# motores.net
KiCad netlist of a schematic drawn in EAGLE
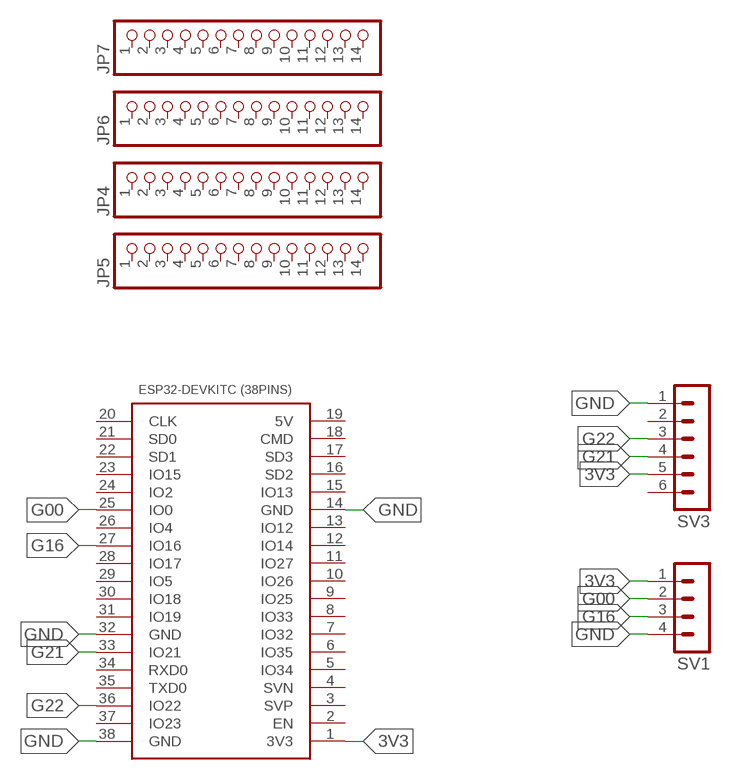
[diagram p0: schematic, sheet 1]

(export (version "E")
  (design (tool "Eeschema 10.0.6"))
  (components
    (comp (ref "ESP32-DEVKITC(38PINS)1")
      (value "ESP32DEVKITC_38PINS")
      (footprint "eagle-import:ESP32-DEVKITC")
      (libsource (lib "eagle-import") (part "ESP32DEVKITC_38PINS"))
    )
    (comp (ref "JP4")
      (value "PINHD-1X14")
      (footprint "eagle-import:1X14")
      (libsource (lib "eagle-import") (part "PINHD-1X14"))
    )
    (comp (ref "JP5")
      (value "PINHD-1X14")
      (footprint "eagle-import:1X14")
      (libsource (lib "eagle-import") (part "PINHD-1X14"))
    )
    (comp (ref "JP6")
      (value "PINHD-1X14")
      (footprint "eagle-import:1X14")
      (libsource (lib "eagle-import") (part "PINHD-1X14"))
    )
    (comp (ref "JP7")
      (value "PINHD-1X14")
      (footprint "eagle-import:1X14")
      (libsource (lib "eagle-import") (part "PINHD-1X14"))
    )
    (comp (ref "SV1")
      (value "MA04-1")
      (footprint "eagle-import:MA04-1")
      (libsource (lib "eagle-import") (part "MA04-1"))
    )
    (comp (ref "SV3")
      (value "MA06-1")
      (footprint "eagle-import:MA06-1")
      (libsource (lib "eagle-import") (part "MA06-1"))
    )
  )
  (nets
    (net (code "1") (name "3V3") (class "Default")
      (node (ref "ESP32-DEVKITC(38PINS)1") (pin "1") (pinfunction "3V3_1") (pintype "bidirectional"))
      (node (ref "SV1") (pin "1") (pinfunction "1_1") (pintype "passive"))
      (node (ref "SV3") (pin "5") (pinfunction "5_5") (pintype "passive"))
    )
    (net (code "2") (name "G00") (class "Default")
      (node (ref "ESP32-DEVKITC(38PINS)1") (pin "25") (pinfunction "IO0_25") (pintype "bidirectional"))
      (node (ref "SV1") (pin "2") (pinfunction "2_2") (pintype "passive"))
    )
    (net (code "3") (name "G16") (class "Default")
      (node (ref "ESP32-DEVKITC(38PINS)1") (pin "27") (pinfunction "IO16_27") (pintype "bidirectional"))
      (node (ref "SV1") (pin "3") (pinfunction "3_3") (pintype "passive"))
    )
    (net (code "4") (name "G21") (class "Default")
      (node (ref "ESP32-DEVKITC(38PINS)1") (pin "33") (pinfunction "IO21_33") (pintype "bidirectional"))
      (node (ref "SV3") (pin "4") (pinfunction "4_4") (pintype "passive"))
    )
    (net (code "5") (name "G22") (class "Default")
      (node (ref "ESP32-DEVKITC(38PINS)1") (pin "36") (pinfunction "IO22_36") (pintype "bidirectional"))
      (node (ref "SV3") (pin "3") (pinfunction "3_3") (pintype "passive"))
    )
    (net (code "6") (name "GND") (class "Default")
      (node (ref "ESP32-DEVKITC(38PINS)1") (pin "14") (pinfunction "GND_14") (pintype "bidirectional"))
      (node (ref "ESP32-DEVKITC(38PINS)1") (pin "32") (pinfunction "GND_32") (pintype "bidirectional"))
      (node (ref "ESP32-DEVKITC(38PINS)1") (pin "38") (pinfunction "GND_38") (pintype "bidirectional"))
      (node (ref "SV1") (pin "4") (pinfunction "4_4") (pintype "passive"))
      (node (ref "SV3") (pin "1") (pinfunction "1_1") (pintype "passive"))
    )
    (net (code "7") (name "unconnected-(ESP32-DEVKITC(38PINS)1-5V-Pad19)") (class "Default")
      (node (ref "ESP32-DEVKITC(38PINS)1") (pin "19") (pinfunction "5V_19") (pintype "bidirectional"))
    )
    (net (code "8") (name "unconnected-(ESP32-DEVKITC(38PINS)1-CLK-Pad20)") (class "Default")
      (node (ref "ESP32-DEVKITC(38PINS)1") (pin "20") (pinfunction "CLK_20") (pintype "bidirectional"))
    )
    (net (code "9") (name "unconnected-(ESP32-DEVKITC(38PINS)1-CMD-Pad18)") (class "Default")
      (node (ref "ESP32-DEVKITC(38PINS)1") (pin "18") (pinfunction "CMD_18") (pintype "bidirectional"))
    )
    (net (code "10") (name "unconnected-(ESP32-DEVKITC(38PINS)1-EN-Pad2)") (class "Default")
      (node (ref "ESP32-DEVKITC(38PINS)1") (pin "2") (pinfunction "EN_2") (pintype "bidirectional"))
    )
    (net (code "11") (name "unconnected-(ESP32-DEVKITC(38PINS)1-IO2-Pad24)") (class "Default")
      (node (ref "ESP32-DEVKITC(38PINS)1") (pin "24") (pinfunction "IO2_24") (pintype "bidirectional"))
    )
    (net (code "12") (name "unconnected-(ESP32-DEVKITC(38PINS)1-IO4-Pad26)") (class "Default")
      (node (ref "ESP32-DEVKITC(38PINS)1") (pin "26") (pinfunction "IO4_26") (pintype "bidirectional"))
    )
    (net (code "13") (name "unconnected-(ESP32-DEVKITC(38PINS)1-IO5-Pad29)") (class "Default")
      (node (ref "ESP32-DEVKITC(38PINS)1") (pin "29") (pinfunction "IO5_29") (pintype "bidirectional"))
    )
    (net (code "14") (name "unconnected-(ESP32-DEVKITC(38PINS)1-IO12-Pad13)") (class "Default")
      (node (ref "ESP32-DEVKITC(38PINS)1") (pin "13") (pinfunction "IO12_13") (pintype "bidirectional"))
    )
    (net (code "15") (name "unconnected-(ESP32-DEVKITC(38PINS)1-IO13-Pad15)") (class "Default")
      (node (ref "ESP32-DEVKITC(38PINS)1") (pin "15") (pinfunction "IO13_15") (pintype "bidirectional"))
    )
    (net (code "16") (name "unconnected-(ESP32-DEVKITC(38PINS)1-IO14-Pad12)") (class "Default")
      (node (ref "ESP32-DEVKITC(38PINS)1") (pin "12") (pinfunction "IO14_12") (pintype "bidirectional"))
    )
    (net (code "17") (name "unconnected-(ESP32-DEVKITC(38PINS)1-IO15-Pad23)") (class "Default")
      (node (ref "ESP32-DEVKITC(38PINS)1") (pin "23") (pinfunction "IO15_23") (pintype "bidirectional"))
    )
    (net (code "18") (name "unconnected-(ESP32-DEVKITC(38PINS)1-IO17-Pad28)") (class "Default")
      (node (ref "ESP32-DEVKITC(38PINS)1") (pin "28") (pinfunction "IO17_28") (pintype "bidirectional"))
    )
    (net (code "19") (name "unconnected-(ESP32-DEVKITC(38PINS)1-IO18-Pad30)") (class "Default")
      (node (ref "ESP32-DEVKITC(38PINS)1") (pin "30") (pinfunction "IO18_30") (pintype "bidirectional"))
    )
    (net (code "20") (name "unconnected-(ESP32-DEVKITC(38PINS)1-IO19-Pad31)") (class "Default")
      (node (ref "ESP32-DEVKITC(38PINS)1") (pin "31") (pinfunction "IO19_31") (pintype "bidirectional"))
    )
    (net (code "21") (name "unconnected-(ESP32-DEVKITC(38PINS)1-IO23-Pad37)") (class "Default")
      (node (ref "ESP32-DEVKITC(38PINS)1") (pin "37") (pinfunction "IO23_37") (pintype "bidirectional"))
    )
    (net (code "22") (name "unconnected-(ESP32-DEVKITC(38PINS)1-IO25-Pad9)") (class "Default")
      (node (ref "ESP32-DEVKITC(38PINS)1") (pin "9") (pinfunction "IO25_9") (pintype "bidirectional"))
    )
    (net (code "23") (name "unconnected-(ESP32-DEVKITC(38PINS)1-IO26-Pad10)") (class "Default")
      (node (ref "ESP32-DEVKITC(38PINS)1") (pin "10") (pinfunction "IO26_10") (pintype "bidirectional"))
    )
    (net (code "24") (name "unconnected-(ESP32-DEVKITC(38PINS)1-IO27-Pad11)") (class "Default")
      (node (ref "ESP32-DEVKITC(38PINS)1") (pin "11") (pinfunction "IO27_11") (pintype "bidirectional"))
    )
    (net (code "25") (name "unconnected-(ESP32-DEVKITC(38PINS)1-IO32-Pad7)") (class "Default")
      (node (ref "ESP32-DEVKITC(38PINS)1") (pin "7") (pinfunction "IO32_7") (pintype "bidirectional"))
    )
    (net (code "26") (name "unconnected-(ESP32-DEVKITC(38PINS)1-IO33-Pad8)") (class "Default")
      (node (ref "ESP32-DEVKITC(38PINS)1") (pin "8") (pinfunction "IO33_8") (pintype "bidirectional"))
    )
    (net (code "27") (name "unconnected-(ESP32-DEVKITC(38PINS)1-IO34-Pad5)") (class "Default")
      (node (ref "ESP32-DEVKITC(38PINS)1") (pin "5") (pinfunction "IO34_5") (pintype "bidirectional"))
    )
    (net (code "28") (name "unconnected-(ESP32-DEVKITC(38PINS)1-IO35-Pad6)") (class "Default")
      (node (ref "ESP32-DEVKITC(38PINS)1") (pin "6") (pinfunction "IO35_6") (pintype "bidirectional"))
    )
    (net (code "29") (name "unconnected-(ESP32-DEVKITC(38PINS)1-RXD0-Pad34)") (class "Default")
      (node (ref "ESP32-DEVKITC(38PINS)1") (pin "34") (pinfunction "RXD0_34") (pintype "bidirectional"))
    )
    (net (code "30") (name "unconnected-(ESP32-DEVKITC(38PINS)1-SD0-Pad21)") (class "Default")
      (node (ref "ESP32-DEVKITC(38PINS)1") (pin "21") (pinfunction "SD0_21") (pintype "bidirectional"))
    )
    (net (code "31") (name "unconnected-(ESP32-DEVKITC(38PINS)1-SD1-Pad22)") (class "Default")
      (node (ref "ESP32-DEVKITC(38PINS)1") (pin "22") (pinfunction "SD1_22") (pintype "bidirectional"))
    )
    (net (code "32") (name "unconnected-(ESP32-DEVKITC(38PINS)1-SD2-Pad16)") (class "Default")
      (node (ref "ESP32-DEVKITC(38PINS)1") (pin "16") (pinfunction "SD2_16") (pintype "bidirectional"))
    )
    (net (code "33") (name "unconnected-(ESP32-DEVKITC(38PINS)1-SD3-Pad17)") (class "Default")
      (node (ref "ESP32-DEVKITC(38PINS)1") (pin "17") (pinfunction "SD3_17") (pintype "bidirectional"))
    )
    (net (code "34") (name "unconnected-(ESP32-DEVKITC(38PINS)1-SVN-Pad4)") (class "Default")
      (node (ref "ESP32-DEVKITC(38PINS)1") (pin "4") (pinfunction "SVN_4") (pintype "bidirectional"))
    )
    (net (code "35") (name "unconnected-(ESP32-DEVKITC(38PINS)1-SVP-Pad3)") (class "Default")
      (node (ref "ESP32-DEVKITC(38PINS)1") (pin "3") (pinfunction "SVP_3") (pintype "bidirectional"))
    )
    (net (code "36") (name "unconnected-(ESP32-DEVKITC(38PINS)1-TXD0-Pad35)") (class "Default")
      (node (ref "ESP32-DEVKITC(38PINS)1") (pin "35") (pinfunction "TXD0_35") (pintype "bidirectional"))
    )
    (net (code "37") (name "unconnected-(JP4-Pad1)") (class "Default")
      (node (ref "JP4") (pin "1") (pinfunction "1_1") (pintype "passive"))
    )
    (net (code "38") (name "unconnected-(JP4-Pad2)") (class "Default")
      (node (ref "JP4") (pin "2") (pinfunction "2_2") (pintype "passive"))
    )
    (net (code "39") (name "unconnected-(JP4-Pad3)") (class "Default")
      (node (ref "JP4") (pin "3") (pinfunction "3_3") (pintype "passive"))
    )
    (net (code "40") (name "unconnected-(JP4-Pad4)") (class "Default")
      (node (ref "JP4") (pin "4") (pinfunction "4_4") (pintype "passive"))
    )
    (net (code "41") (name "unconnected-(JP4-Pad5)") (class "Default")
      (node (ref "JP4") (pin "5") (pinfunction "5_5") (pintype "passive"))
    )
    (net (code "42") (name "unconnected-(JP4-Pad6)") (class "Default")
      (node (ref "JP4") (pin "6") (pinfunction "6_6") (pintype "passive"))
    )
    (net (code "43") (name "unconnected-(JP4-Pad7)") (class "Default")
      (node (ref "JP4") (pin "7") (pinfunction "7_7") (pintype "passive"))
    )
    (net (code "44") (name "unconnected-(JP4-Pad8)") (class "Default")
      (node (ref "JP4") (pin "8") (pinfunction "8_8") (pintype "passive"))
    )
    (net (code "45") (name "unconnected-(JP4-Pad9)") (class "Default")
      (node (ref "JP4") (pin "9") (pinfunction "9_9") (pintype "passive"))
    )
    (net (code "46") (name "unconnected-(JP4-Pad10)") (class "Default")
      (node (ref "JP4") (pin "10") (pinfunction "10_10") (pintype "passive"))
    )
    (net (code "47") (name "unconnected-(JP4-Pad11)") (class "Default")
      (node (ref "JP4") (pin "11") (pinfunction "11_11") (pintype "passive"))
    )
    (net (code "48") (name "unconnected-(JP4-Pad12)") (class "Default")
      (node (ref "JP4") (pin "12") (pinfunction "12_12") (pintype "passive"))
    )
    (net (code "49") (name "unconnected-(JP4-Pad13)") (class "Default")
      (node (ref "JP4") (pin "13") (pinfunction "13_13") (pintype "passive"))
    )
    (net (code "50") (name "unconnected-(JP4-Pad14)") (class "Default")
      (node (ref "JP4") (pin "14") (pinfunction "14_14") (pintype "passive"))
    )
    (net (code "51") (name "unconnected-(JP5-Pad1)") (class "Default")
      (node (ref "JP5") (pin "1") (pinfunction "1_1") (pintype "passive"))
    )
    (net (code "52") (name "unconnected-(JP5-Pad2)") (class "Default")
      (node (ref "JP5") (pin "2") (pinfunction "2_2") (pintype "passive"))
    )
    (net (code "53") (name "unconnected-(JP5-Pad3)") (class "Default")
      (node (ref "JP5") (pin "3") (pinfunction "3_3") (pintype "passive"))
    )
    (net (code "54") (name "unconnected-(JP5-Pad4)") (class "Default")
      (node (ref "JP5") (pin "4") (pinfunction "4_4") (pintype "passive"))
    )
    (net (code "55") (name "unconnected-(JP5-Pad5)") (class "Default")
      (node (ref "JP5") (pin "5") (pinfunction "5_5") (pintype "passive"))
    )
    (net (code "56") (name "unconnected-(JP5-Pad6)") (class "Default")
      (node (ref "JP5") (pin "6") (pinfunction "6_6") (pintype "passive"))
    )
    (net (code "57") (name "unconnected-(JP5-Pad7)") (class "Default")
      (node (ref "JP5") (pin "7") (pinfunction "7_7") (pintype "passive"))
    )
    (net (code "58") (name "unconnected-(JP5-Pad8)") (class "Default")
      (node (ref "JP5") (pin "8") (pinfunction "8_8") (pintype "passive"))
    )
    (net (code "59") (name "unconnected-(JP5-Pad9)") (class "Default")
      (node (ref "JP5") (pin "9") (pinfunction "9_9") (pintype "passive"))
    )
    (net (code "60") (name "unconnected-(JP5-Pad10)") (class "Default")
      (node (ref "JP5") (pin "10") (pinfunction "10_10") (pintype "passive"))
    )
    (net (code "61") (name "unconnected-(JP5-Pad11)") (class "Default")
      (node (ref "JP5") (pin "11") (pinfunction "11_11") (pintype "passive"))
    )
    (net (code "62") (name "unconnected-(JP5-Pad12)") (class "Default")
      (node (ref "JP5") (pin "12") (pinfunction "12_12") (pintype "passive"))
    )
    (net (code "63") (name "unconnected-(JP5-Pad13)") (class "Default")
      (node (ref "JP5") (pin "13") (pinfunction "13_13") (pintype "passive"))
    )
    (net (code "64") (name "unconnected-(JP5-Pad14)") (class "Default")
      (node (ref "JP5") (pin "14") (pinfunction "14_14") (pintype "passive"))
    )
    (net (code "65") (name "unconnected-(JP6-Pad1)") (class "Default")
      (node (ref "JP6") (pin "1") (pinfunction "1_1") (pintype "passive"))
    )
    (net (code "66") (name "unconnected-(JP6-Pad2)") (class "Default")
      (node (ref "JP6") (pin "2") (pinfunction "2_2") (pintype "passive"))
    )
    (net (code "67") (name "unconnected-(JP6-Pad3)") (class "Default")
      (node (ref "JP6") (pin "3") (pinfunction "3_3") (pintype "passive"))
    )
    (net (code "68") (name "unconnected-(JP6-Pad4)") (class "Default")
      (node (ref "JP6") (pin "4") (pinfunction "4_4") (pintype "passive"))
    )
    (net (code "69") (name "unconnected-(JP6-Pad5)") (class "Default")
      (node (ref "JP6") (pin "5") (pinfunction "5_5") (pintype "passive"))
    )
    (net (code "70") (name "unconnected-(JP6-Pad6)") (class "Default")
      (node (ref "JP6") (pin "6") (pinfunction "6_6") (pintype "passive"))
    )
    (net (code "71") (name "unconnected-(JP6-Pad7)") (class "Default")
      (node (ref "JP6") (pin "7") (pinfunction "7_7") (pintype "passive"))
    )
    (net (code "72") (name "unconnected-(JP6-Pad8)") (class "Default")
      (node (ref "JP6") (pin "8") (pinfunction "8_8") (pintype "passive"))
    )
    (net (code "73") (name "unconnected-(JP6-Pad9)") (class "Default")
      (node (ref "JP6") (pin "9") (pinfunction "9_9") (pintype "passive"))
    )
    (net (code "74") (name "unconnected-(JP6-Pad10)") (class "Default")
      (node (ref "JP6") (pin "10") (pinfunction "10_10") (pintype "passive"))
    )
    (net (code "75") (name "unconnected-(JP6-Pad11)") (class "Default")
      (node (ref "JP6") (pin "11") (pinfunction "11_11") (pintype "passive"))
    )
    (net (code "76") (name "unconnected-(JP6-Pad12)") (class "Default")
      (node (ref "JP6") (pin "12") (pinfunction "12_12") (pintype "passive"))
    )
    (net (code "77") (name "unconnected-(JP6-Pad13)") (class "Default")
      (node (ref "JP6") (pin "13") (pinfunction "13_13") (pintype "passive"))
    )
    (net (code "78") (name "unconnected-(JP6-Pad14)") (class "Default")
      (node (ref "JP6") (pin "14") (pinfunction "14_14") (pintype "passive"))
    )
    (net (code "79") (name "unconnected-(JP7-Pad1)") (class "Default")
      (node (ref "JP7") (pin "1") (pinfunction "1_1") (pintype "passive"))
    )
    (net (code "80") (name "unconnected-(JP7-Pad2)") (class "Default")
      (node (ref "JP7") (pin "2") (pinfunction "2_2") (pintype "passive"))
    )
    (net (code "81") (name "unconnected-(JP7-Pad3)") (class "Default")
      (node (ref "JP7") (pin "3") (pinfunction "3_3") (pintype "passive"))
    )
    (net (code "82") (name "unconnected-(JP7-Pad4)") (class "Default")
      (node (ref "JP7") (pin "4") (pinfunction "4_4") (pintype "passive"))
    )
    (net (code "83") (name "unconnected-(JP7-Pad5)") (class "Default")
      (node (ref "JP7") (pin "5") (pinfunction "5_5") (pintype "passive"))
    )
    (net (code "84") (name "unconnected-(JP7-Pad6)") (class "Default")
      (node (ref "JP7") (pin "6") (pinfunction "6_6") (pintype "passive"))
    )
    (net (code "85") (name "unconnected-(JP7-Pad7)") (class "Default")
      (node (ref "JP7") (pin "7") (pinfunction "7_7") (pintype "passive"))
    )
    (net (code "86") (name "unconnected-(JP7-Pad8)") (class "Default")
      (node (ref "JP7") (pin "8") (pinfunction "8_8") (pintype "passive"))
    )
    (net (code "87") (name "unconnected-(JP7-Pad9)") (class "Default")
      (node (ref "JP7") (pin "9") (pinfunction "9_9") (pintype "passive"))
    )
    (net (code "88") (name "unconnected-(JP7-Pad10)") (class "Default")
      (node (ref "JP7") (pin "10") (pinfunction "10_10") (pintype "passive"))
    )
    (net (code "89") (name "unconnected-(JP7-Pad11)") (class "Default")
      (node (ref "JP7") (pin "11") (pinfunction "11_11") (pintype "passive"))
    )
    (net (code "90") (name "unconnected-(JP7-Pad12)") (class "Default")
      (node (ref "JP7") (pin "12") (pinfunction "12_12") (pintype "passive"))
    )
    (net (code "91") (name "unconnected-(JP7-Pad13)") (class "Default")
      (node (ref "JP7") (pin "13") (pinfunction "13_13") (pintype "passive"))
    )
    (net (code "92") (name "unconnected-(JP7-Pad14)") (class "Default")
      (node (ref "JP7") (pin "14") (pinfunction "14_14") (pintype "passive"))
    )
    (net (code "93") (name "unconnected-(SV3-Pad2)") (class "Default")
      (node (ref "SV3") (pin "2") (pinfunction "2_2") (pintype "passive"))
    )
    (net (code "94") (name "unconnected-(SV3-Pad6)") (class "Default")
      (node (ref "SV3") (pin "6") (pinfunction "6_6") (pintype "passive"))
    )
  )
)
